# STM32WB55CGU6.net
KiCad netlist of a schematic drawn in Altium Designer
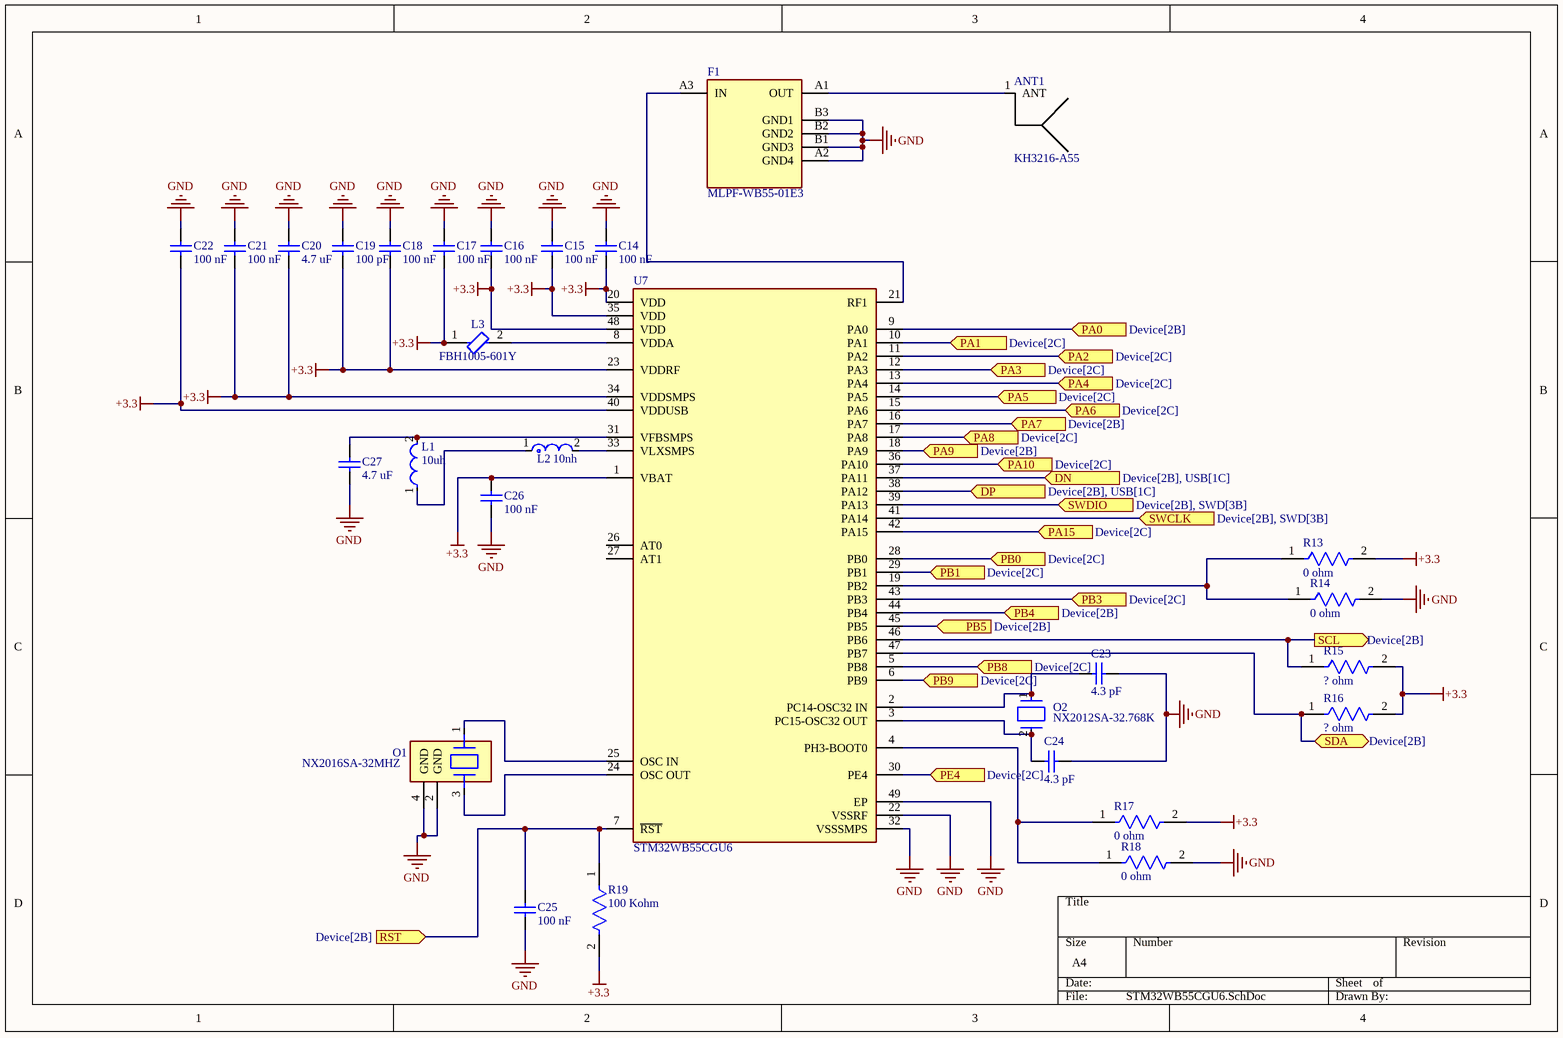
[diagram p0: STM32WB55CGU6.SchDoc]

(export (version "E")
  (design (tool "Eeschema 10.0.6"))
  (components
    (comp (ref "ANT1")
      (value "KH3216-A55")
      (footprint "KH3216-A55")
      (libsource (lib "ANT") (part "KH3216-A55"))
    )
    (comp (ref "C14")
      (value "100 nF")
      (footprint "CAPC1005X55X25NL05T10")
      (fields (field (name "MANUFACTURER") "Murata") (field (name "PART NUMBER") "GRM155F50J684ZE01D"))
      (libsource (lib "Altium Content Vault") (part "CAP"))
    )
    (comp (ref "C15")
      (value "100 nF")
      (footprint "CAPC1005X55X25NL05T10")
      (fields (field (name "MANUFACTURER") "Murata") (field (name "PART NUMBER") "GRM155F50J684ZE01D"))
      (libsource (lib "Altium Content Vault") (part "CAP"))
    )
    (comp (ref "C16")
      (value "100 nF")
      (footprint "CAPC1005X55X25NL05T10")
      (fields (field (name "MANUFACTURER") "Murata") (field (name "PART NUMBER") "GRM155F50J684ZE01D"))
      (libsource (lib "Altium Content Vault") (part "CAP"))
    )
    (comp (ref "C17")
      (value "100 nF")
      (footprint "CAPC1005X55X25NL05T10")
      (fields (field (name "MANUFACTURER") "Murata") (field (name "PART NUMBER") "GRM155F50J684ZE01D"))
      (libsource (lib "Altium Content Vault") (part "CAP"))
    )
    (comp (ref "C18")
      (value "100 nF")
      (footprint "CAPC1005X55X25NL05T10")
      (fields (field (name "MANUFACTURER") "Murata") (field (name "PART NUMBER") "GRM155F50J684ZE01D"))
      (libsource (lib "Altium Content Vault") (part "CAP"))
    )
    (comp (ref "C19")
      (value "100 pF")
      (footprint "CAPC1005X55X25NL05T10")
      (fields (field (name "MANUFACTURER") "Murata") (field (name "PART NUMBER") "GRM155F50J684ZE01D"))
      (libsource (lib "Altium Content Vault") (part "CAP"))
    )
    (comp (ref "C20")
      (value "4.7 uF")
      (footprint "CAPC1005X55X25NL05T10")
      (fields (field (name "MANUFACTURER") "Murata") (field (name "PART NUMBER") "GRM155F50J684ZE01D"))
      (libsource (lib "Altium Content Vault") (part "CAP"))
    )
    (comp (ref "C21")
      (value "100 nF")
      (footprint "CAPC1005X55X25NL05T10")
      (fields (field (name "MANUFACTURER") "Murata") (field (name "PART NUMBER") "GRM155F50J684ZE01D"))
      (libsource (lib "Altium Content Vault") (part "CAP"))
    )
    (comp (ref "C22")
      (value "100 nF")
      (footprint "CAPC1005X55X25NL05T10")
      (fields (field (name "MANUFACTURER") "Murata") (field (name "PART NUMBER") "GRM155F50J684ZE01D"))
      (libsource (lib "Altium Content Vault") (part "CAP"))
    )
    (comp (ref "C23")
      (value "4.3 pF")
      (footprint "CAPC1005X55X25NL05T10")
      (fields (field (name "MANUFACTURER") "Murata") (field (name "PART NUMBER") "GRM155F50J684ZE01D"))
      (libsource (lib "Altium Content Vault") (part "CAP"))
    )
    (comp (ref "C24")
      (value "4.3 pF")
      (footprint "CAPC1005X55X25NL05T10")
      (fields (field (name "MANUFACTURER") "Murata") (field (name "PART NUMBER") "GRM155F50J684ZE01D"))
      (libsource (lib "Altium Content Vault") (part "CAP"))
    )
    (comp (ref "C25")
      (value "100 nF")
      (footprint "CAPC1005X55X25NL05T10")
      (fields (field (name "MANUFACTURER") "Murata") (field (name "PART NUMBER") "GRM155F50J684ZE01D"))
      (libsource (lib "Altium Content Vault") (part "CAP"))
    )
    (comp (ref "C26")
      (value "100 nF")
      (footprint "CAPC1005X55X25NL05T10")
      (fields (field (name "MANUFACTURER") "Murata") (field (name "PART NUMBER") "GRM155F50J684ZE01D"))
      (libsource (lib "Altium Content Vault") (part "CAP"))
    )
    (comp (ref "C27")
      (value "4.7 uF")
      (footprint "CAPC1005X55X25NL05T10")
      (fields (field (name "MANUFACTURER") "Murata") (field (name "PART NUMBER") "GRM155F50J684ZE01D"))
      (libsource (lib "Altium Content Vault") (part "CAP"))
    )
    (comp (ref "F1")
      (value "MLPF-WB55-01E3")
      (footprint "FP-MLPF-WB55-01E3-MFG")
      (description "RF FILTER LOW PASS 2.45GHZ 6SMD")
      (libsource (lib "Altium Content Vault") (part "51e28da9fe7b2e4e5e03ac85244eada"))
    )
    (comp (ref "L1")
      (value "10uh")
      (footprint "FP-LQM21FN_70-MFG")
      (description "FIXED IND 10UH 100MA 780MOHM SMD")
      (fields (field (name "TOLERANCE") "20%"))
      (libsource (lib "Altium Content Vault") (part "725321dda6339637d4d059423bc1c3c"))
    )
    (comp (ref "L2")
      (value "10nh")
      (footprint "FP-LQG15WH_02-MFG")
      (description "Multilayer type Inductor for Automotive 10nH ±5% 0.19Ω 500mA 0402")
      (fields (field (name "TOLERANCE") "5%"))
      (libsource (lib "Altium Content Vault") (part "4cc4b267dca4c8e51f7102f422741d8"))
    )
    (comp (ref "L3")
      (value "FBH1005-601Y")
      (footprint "FP-BLM15-0_05-MFG")
      (description "Chip Ferrite Bead, 0402, 600Ω @ 100MHz, 0.52Ω, 25%, 300mA")
      (fields (field (name "TOLERANCE") "25%"))
      (libsource (lib "Altium Content Vault") (part "5f30dd21d616792df468990f7003faa"))
    )
    (comp (ref "O1")
      (value "NX2016SA-32MHZ")
      (footprint "FP-NX2016SA-MFG")
      (description "CRYSTAL 32.0000MHZ 8PF SMD")
      (libsource (lib "Altium Content Vault") (part "0d11ad3ca7be055efd3b4f344707230"))
    )
    (comp (ref "O2")
      (value "NX2012SA-32.768K")
      (footprint "FP-NX2012SA-MFG")
      (description "CRYSTAL 32.7680KHZ 12.5PF SMD")
      (libsource (lib "Altium Content Vault") (part "c23a69dc6c9e2f18f2079038eb95dd1"))
    )
    (comp (ref "R13")
      (value "0 ohm")
      (footprint "FP-RC1005-IPC_C")
      (description "Res Thick Film 0402 1.87kΩ 1% 0.063W ±100ppm/°C Molded SMD T/R")
      (fields (field (name "TOLERANCE") "1%"))
      (libsource (lib "Altium Content Vault") (part "1029c3af85768c4190bb7ad29bc67b5"))
    )
    (comp (ref "R14")
      (value "0 ohm")
      (footprint "FP-RC1005-IPC_C")
      (description "Res Thick Film 0402 1.87kΩ 1% 0.063W ±100ppm/°C Molded SMD T/R")
      (fields (field (name "TOLERANCE") "1%"))
      (libsource (lib "Altium Content Vault") (part "1029c3af85768c4190bb7ad29bc67b5"))
    )
    (comp (ref "R15")
      (value "? ohm")
      (footprint "FP-RC1005-IPC_C")
      (description "Res Thick Film 0402 1.87kΩ 1% 0.063W ±100ppm/°C Molded SMD T/R")
      (fields (field (name "TOLERANCE") "1%"))
      (libsource (lib "Altium Content Vault") (part "1029c3af85768c4190bb7ad29bc67b5"))
    )
    (comp (ref "R16")
      (value "? ohm")
      (footprint "FP-RC1005-IPC_C")
      (description "Res Thick Film 0402 1.87kΩ 1% 0.063W ±100ppm/°C Molded SMD T/R")
      (fields (field (name "TOLERANCE") "1%"))
      (libsource (lib "Altium Content Vault") (part "1029c3af85768c4190bb7ad29bc67b5"))
    )
    (comp (ref "R17")
      (value "0 ohm")
      (footprint "FP-RC1005-IPC_C")
      (description "Res Thick Film 0402 1.87kΩ 1% 0.063W ±100ppm/°C Molded SMD T/R")
      (fields (field (name "TOLERANCE") "1%"))
      (libsource (lib "Altium Content Vault") (part "1029c3af85768c4190bb7ad29bc67b5"))
    )
    (comp (ref "R18")
      (value "0 ohm")
      (footprint "FP-RC1005-IPC_C")
      (description "Res Thick Film 0402 1.87kΩ 1% 0.063W ±100ppm/°C Molded SMD T/R")
      (fields (field (name "TOLERANCE") "1%"))
      (libsource (lib "Altium Content Vault") (part "1029c3af85768c4190bb7ad29bc67b5"))
    )
    (comp (ref "R19")
      (value "100 Kohm")
      (footprint "FP-RC1005-IPC_C")
      (description "Res Thick Film 0402 1.87kΩ 1% 0.063W ±100ppm/°C Molded SMD T/R")
      (fields (field (name "TOLERANCE") "1%"))
      (libsource (lib "Altium Content Vault") (part "1029c3af85768c4190bb7ad29bc67b5"))
    )
    (comp (ref "U7")
      (value "STM32WB55CGU6")
      (footprint "FP-STM32WB55CGU6-MFG")
      (description "ULTRA-LOW-POWER DUAL CORE ARM CO")
      (fields
        (field (name "OCTOPART") "https://octopart.com/stm32wb55cgu6-stmicroelectronics-98750847")
        (field (name "MANUFACTURER") "STMicroelectronics")
      )
      (libsource (lib "Altium Content Vault") (part "9d9ca7f3567da95c474f3f549f05e68"))
    )
  )
  (nets
    (net (code "1") (name "+3.3") (class "Default")
      (node (ref "C14") (pin "1") (pinfunction "1_1") (pintype "passive"))
      (node (ref "C15") (pin "2") (pinfunction "2_2") (pintype "passive"))
      (node (ref "C16") (pin "1") (pinfunction "1_1") (pintype "passive"))
      (node (ref "C17") (pin "2") (pinfunction "2_2") (pintype "passive"))
      (node (ref "C18") (pin "1") (pinfunction "1_1") (pintype "passive"))
      (node (ref "C19") (pin "2") (pinfunction "2_2") (pintype "passive"))
      (node (ref "C20") (pin "2") (pinfunction "2_2") (pintype "passive"))
      (node (ref "C21") (pin "1") (pinfunction "1_1") (pintype "passive"))
      (node (ref "C22") (pin "2") (pinfunction "2_2") (pintype "passive"))
      (node (ref "C26") (pin "2") (pinfunction "2_2") (pintype "passive"))
      (node (ref "L3") (pin "1") (pinfunction "1_1") (pintype "passive"))
      (node (ref "R13") (pin "2") (pinfunction "2_2") (pintype "passive"))
      (node (ref "R15") (pin "2") (pinfunction "2_2") (pintype "passive"))
      (node (ref "R16") (pin "2") (pinfunction "2_2") (pintype "passive"))
      (node (ref "R17") (pin "2") (pinfunction "2_2") (pintype "passive"))
      (node (ref "R19") (pin "2") (pinfunction "2_2") (pintype "passive"))
      (node (ref "U7") (pin "1") (pinfunction "VBAT_1") (pintype "passive"))
      (node (ref "U7") (pin "20") (pinfunction "VDD_20") (pintype "passive"))
      (node (ref "U7") (pin "23") (pinfunction "VDDRF_23") (pintype "passive"))
      (node (ref "U7") (pin "34") (pinfunction "VDDSMPS_34") (pintype "passive"))
      (node (ref "U7") (pin "35") (pinfunction "VDD_35") (pintype "passive"))
      (node (ref "U7") (pin "40") (pinfunction "VDDUSB_40") (pintype "passive"))
      (node (ref "U7") (pin "48") (pinfunction "VDD_48") (pintype "passive"))
    )
    (net (code "2") (name "/DN") (class "Default")
      (node (ref "U7") (pin "37") (pinfunction "PA11_37") (pintype "passive"))
    )
    (net (code "3") (name "/DP") (class "Default")
      (node (ref "U7") (pin "38") (pinfunction "PA12_38") (pintype "passive"))
    )
    (net (code "4") (name "/PA0") (class "Default")
      (node (ref "U7") (pin "9") (pinfunction "PA0_9") (pintype "passive"))
    )
    (net (code "5") (name "/PA1") (class "Default")
      (node (ref "U7") (pin "10") (pinfunction "PA1_10") (pintype "passive"))
    )
    (net (code "6") (name "/PA2") (class "Default")
      (node (ref "U7") (pin "11") (pinfunction "PA2_11") (pintype "passive"))
    )
    (net (code "7") (name "/PA3") (class "Default")
      (node (ref "U7") (pin "12") (pinfunction "PA3_12") (pintype "passive"))
    )
    (net (code "8") (name "/PA4") (class "Default")
      (node (ref "U7") (pin "13") (pinfunction "PA4_13") (pintype "passive"))
    )
    (net (code "9") (name "/PA5") (class "Default")
      (node (ref "U7") (pin "14") (pinfunction "PA5_14") (pintype "passive"))
    )
    (net (code "10") (name "/PA6") (class "Default")
      (node (ref "U7") (pin "15") (pinfunction "PA6_15") (pintype "passive"))
    )
    (net (code "11") (name "/PA7") (class "Default")
      (node (ref "U7") (pin "16") (pinfunction "PA7_16") (pintype "passive"))
    )
    (net (code "12") (name "/PA8") (class "Default")
      (node (ref "U7") (pin "17") (pinfunction "PA8_17") (pintype "passive"))
    )
    (net (code "13") (name "/PA9") (class "Default")
      (node (ref "U7") (pin "18") (pinfunction "PA9_18") (pintype "passive"))
    )
    (net (code "14") (name "/PA10") (class "Default")
      (node (ref "U7") (pin "36") (pinfunction "PA10_36") (pintype "passive"))
    )
    (net (code "15") (name "/PA15") (class "Default")
      (node (ref "U7") (pin "42") (pinfunction "PA15_42") (pintype "passive"))
    )
    (net (code "16") (name "/PB0") (class "Default")
      (node (ref "U7") (pin "28") (pinfunction "PB0_28") (pintype "passive"))
    )
    (net (code "17") (name "/PB1") (class "Default")
      (node (ref "U7") (pin "29") (pinfunction "PB1_29") (pintype "passive"))
    )
    (net (code "18") (name "/PB3") (class "Default")
      (node (ref "U7") (pin "43") (pinfunction "PB3_43") (pintype "passive"))
    )
    (net (code "19") (name "/PB4") (class "Default")
      (node (ref "U7") (pin "44") (pinfunction "PB4_44") (pintype "passive"))
    )
    (net (code "20") (name "/PB5") (class "Default")
      (node (ref "U7") (pin "45") (pinfunction "PB5_45") (pintype "passive"))
    )
    (net (code "21") (name "/PB8") (class "Default")
      (node (ref "U7") (pin "5") (pinfunction "PB8_5") (pintype "passive"))
    )
    (net (code "22") (name "/PB9") (class "Default")
      (node (ref "U7") (pin "6") (pinfunction "PB9_6") (pintype "passive"))
    )
    (net (code "23") (name "/PE4") (class "Default")
      (node (ref "U7") (pin "30") (pinfunction "PE4_30") (pintype "passive"))
    )
    (net (code "24") (name "/RST") (class "Default")
      (node (ref "C25") (pin "2") (pinfunction "2_2") (pintype "passive"))
      (node (ref "R19") (pin "1") (pinfunction "1_1") (pintype "passive"))
      (node (ref "U7") (pin "7") (pinfunction "~{RST}_7") (pintype "passive"))
    )
    (net (code "25") (name "/SCL") (class "Default")
      (node (ref "R15") (pin "1") (pinfunction "1_1") (pintype "passive"))
      (node (ref "U7") (pin "46") (pinfunction "PB6_46") (pintype "passive"))
    )
    (net (code "26") (name "/SDA") (class "Default")
      (node (ref "R16") (pin "1") (pinfunction "1_1") (pintype "passive"))
      (node (ref "U7") (pin "47") (pinfunction "PB7_47") (pintype "passive"))
    )
    (net (code "27") (name "/SWCLK") (class "Default")
      (node (ref "U7") (pin "41") (pinfunction "PA14_41") (pintype "passive"))
    )
    (net (code "28") (name "/SWDIO") (class "Default")
      (node (ref "U7") (pin "39") (pinfunction "PA13_39") (pintype "passive"))
    )
    (net (code "29") (name "GND") (class "Default")
      (node (ref "C14") (pin "2") (pinfunction "2_2") (pintype "passive"))
      (node (ref "C15") (pin "1") (pinfunction "1_1") (pintype "passive"))
      (node (ref "C16") (pin "2") (pinfunction "2_2") (pintype "passive"))
      (node (ref "C17") (pin "1") (pinfunction "1_1") (pintype "passive"))
      (node (ref "C18") (pin "2") (pinfunction "2_2") (pintype "passive"))
      (node (ref "C19") (pin "1") (pinfunction "1_1") (pintype "passive"))
      (node (ref "C20") (pin "1") (pinfunction "1_1") (pintype "passive"))
      (node (ref "C21") (pin "2") (pinfunction "2_2") (pintype "passive"))
      (node (ref "C22") (pin "1") (pinfunction "1_1") (pintype "passive"))
      (node (ref "C23") (pin "2") (pinfunction "2_2") (pintype "passive"))
      (node (ref "C24") (pin "1") (pinfunction "1_1") (pintype "passive"))
      (node (ref "C25") (pin "1") (pinfunction "1_1") (pintype "passive"))
      (node (ref "C26") (pin "1") (pinfunction "1_1") (pintype "passive"))
      (node (ref "C27") (pin "2") (pinfunction "2_2") (pintype "passive"))
      (node (ref "F1") (pin "A2") (pinfunction "GND4_A2") (pintype "power_in"))
      (node (ref "F1") (pin "B1") (pinfunction "GND3_B1") (pintype "power_in"))
      (node (ref "F1") (pin "B2") (pinfunction "GND2_B2") (pintype "power_in"))
      (node (ref "F1") (pin "B3") (pinfunction "GND1_B3") (pintype "power_in"))
      (node (ref "O1") (pin "2") (pinfunction "GND_2") (pintype "power_in"))
      (node (ref "O1") (pin "4") (pinfunction "GND_4") (pintype "power_in"))
      (node (ref "R14") (pin "2") (pinfunction "2_2") (pintype "passive"))
      (node (ref "R18") (pin "2") (pinfunction "2_2") (pintype "passive"))
      (node (ref "U7") (pin "22") (pinfunction "VSSRF_22") (pintype "passive"))
      (node (ref "U7") (pin "32") (pinfunction "VSSSMPS_32") (pintype "passive"))
      (node (ref "U7") (pin "49") (pinfunction "EP_49") (pintype "power_in"))
    )
    (net (code "30") (name "Net-(ANT1-ANT)") (class "Default")
      (node (ref "ANT1") (pin "1") (pinfunction "ANT_1") (pintype "passive"))
      (node (ref "F1") (pin "A1") (pinfunction "OUT_A1") (pintype "passive"))
    )
    (net (code "31") (name "Net-(F1-IN)") (class "Default")
      (node (ref "F1") (pin "A3") (pinfunction "IN_A3") (pintype "power_in"))
      (node (ref "U7") (pin "21") (pinfunction "RF1_21") (pintype "passive"))
    )
    (net (code "32") (name "Net-(L1-Pad1)") (class "Default")
      (node (ref "L1") (pin "1") (pinfunction "1_1") (pintype "passive"))
      (node (ref "L2") (pin "1") (pinfunction "1_1") (pintype "passive"))
    )
    (net (code "33") (name "Net-(U7-OSC_IN)") (class "Default")
      (node (ref "O1") (pin "1") (pinfunction "1_1") (pintype "passive"))
      (node (ref "U7") (pin "25") (pinfunction "OSC_IN_25") (pintype "passive"))
    )
    (net (code "34") (name "Net-(U7-OSC_OUT)") (class "Default")
      (node (ref "O1") (pin "3") (pinfunction "3_3") (pintype "passive"))
      (node (ref "U7") (pin "24") (pinfunction "OSC_OUT_24") (pintype "passive"))
    )
    (net (code "35") (name "Net-(U7-PB2)") (class "Default")
      (node (ref "R13") (pin "1") (pinfunction "1_1") (pintype "passive"))
      (node (ref "R14") (pin "1") (pinfunction "1_1") (pintype "passive"))
      (node (ref "U7") (pin "19") (pinfunction "PB2_19") (pintype "passive"))
    )
    (net (code "36") (name "Net-(U7-PC14-OSC32_IN)") (class "Default")
      (node (ref "C23") (pin "1") (pinfunction "1_1") (pintype "passive"))
      (node (ref "O2") (pin "1") (pinfunction "1_1") (pintype "passive"))
      (node (ref "U7") (pin "2") (pinfunction "PC14-OSC32_IN_2") (pintype "passive"))
    )
    (net (code "37") (name "Net-(U7-PC15-OSC32_OUT)") (class "Default")
      (node (ref "C24") (pin "2") (pinfunction "2_2") (pintype "passive"))
      (node (ref "O2") (pin "2") (pinfunction "2_2") (pintype "passive"))
      (node (ref "U7") (pin "3") (pinfunction "PC15-OSC32_OUT_3") (pintype "passive"))
    )
    (net (code "38") (name "Net-(U7-PH3-BOOT0)") (class "Default")
      (node (ref "R17") (pin "1") (pinfunction "1_1") (pintype "passive"))
      (node (ref "R18") (pin "1") (pinfunction "1_1") (pintype "passive"))
      (node (ref "U7") (pin "4") (pinfunction "PH3-BOOT0_4") (pintype "passive"))
    )
    (net (code "39") (name "Net-(U7-VDDA)") (class "Default")
      (node (ref "L3") (pin "2") (pinfunction "2_2") (pintype "passive"))
      (node (ref "U7") (pin "8") (pinfunction "VDDA_8") (pintype "passive"))
    )
    (net (code "40") (name "Net-(U7-VFBSMPS)") (class "Default")
      (node (ref "C27") (pin "1") (pinfunction "1_1") (pintype "passive"))
      (node (ref "L1") (pin "2") (pinfunction "2_2") (pintype "passive"))
      (node (ref "U7") (pin "31") (pinfunction "VFBSMPS_31") (pintype "passive"))
    )
    (net (code "41") (name "Net-(U7-VLXSMPS)") (class "Default")
      (node (ref "L2") (pin "2") (pinfunction "2_2") (pintype "passive"))
      (node (ref "U7") (pin "33") (pinfunction "VLXSMPS_33") (pintype "passive"))
    )
    (net (code "42") (name "unconnected-(U7-AT0-Pad26)") (class "Default")
      (node (ref "U7") (pin "26") (pinfunction "AT0_26") (pintype "passive"))
    )
    (net (code "43") (name "unconnected-(U7-AT1-Pad27)") (class "Default")
      (node (ref "U7") (pin "27") (pinfunction "AT1_27") (pintype "passive"))
    )
  )
)
